# Mini-DSO-WaveGen-in-one.net
KiCad netlist of a schematic drawn in Altium Designer
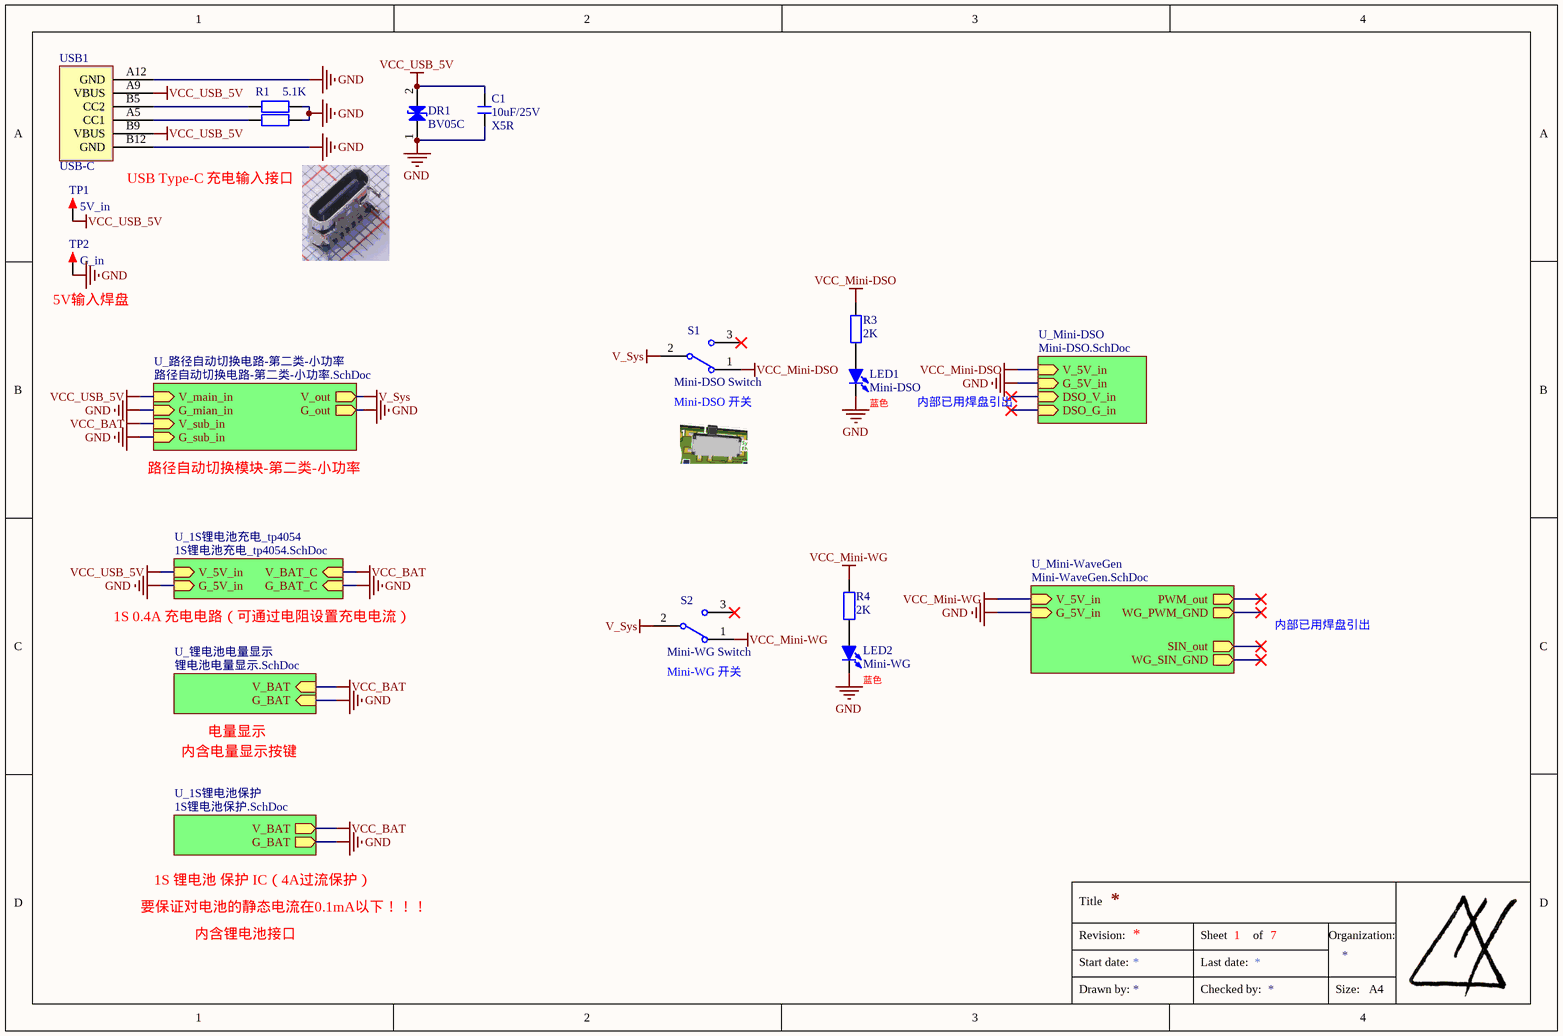
[diagram p0: Mini-DSO-WaveGen-in-one.SchDoc]

(export (version "E")
  (design (tool "Eeschema 10.0.6"))
  (components
    (comp (ref "C1")
      (value "10uF/25V")
      (footprint "C 0603_L")
      (description "无极性贴片电容 X5R")
      (fields (field (name "BOM名称") "X5R"))
      (libsource (lib "Foundation_temp") (part "C X5R"))
    )
    (comp (ref "DR1")
      (value "BV05C")
      (footprint "SOD-323")
      (description "瞬态电压抑制二极管")
      (fields (field (name "版权归属") "源创客"))
      (libsource (lib "8.1   - 二极管-整流桥") (part "DR"))
    )
    (comp (ref "LED1")
      (value "Mini-DSO")
      (footprint "LED 0805R")
      (description "蓝色 贴片LED")
      (fields (field (name "版权归属") "源创客"))
      (libsource (lib "9.1   - LED") (part "LED-SMD"))
    )
    (comp (ref "LED2")
      (value "Mini-WG")
      (footprint "LED 0805R")
      (description "贴片LED 蓝色")
      (fields (field (name "版权归属") "源创客"))
      (libsource (lib "9.1   - LED") (part "LED-SMD"))
    )
    (comp (ref "R1")
      (value "5.1K")
      (footprint "R 0402_L")
      (description "贴片电阻 E-96 1%")
      (libsource (lib "Foundation_temp") (part "R"))
    )
    (comp (ref "R2")
      (value "5.1K")
      (footprint "R 0402_L")
      (description "贴片电阻 E-96 1%")
      (libsource (lib "Foundation_temp") (part "R"))
    )
    (comp (ref "R3")
      (value "2K")
      (footprint "R 0402_L")
      (description "贴片电阻 E-96 1%")
      (libsource (lib "Foundation_temp") (part "R"))
    )
    (comp (ref "R4")
      (value "2K")
      (footprint "R 0402_L")
      (description "贴片电阻 E-96 1%")
      (libsource (lib "Foundation_temp") (part "R"))
    )
    (comp (ref "S1")
      (value "Mini-DSO Switch")
      (footprint "MSK-12C01-07")
      (description "1路拨动开关")
      (fields (field (name "版权归属") "源创客"))
      (libsource (lib "5.1   - 按键-开关") (part "SSW-1P"))
    )
    (comp (ref "S2")
      (value "Mini-WG Switch")
      (footprint "MSK-12C01-07")
      (description "1路拨动开关")
      (fields (field (name "版权归属") "源创客"))
      (libsource (lib "5.1   - 按键-开关") (part "SSW-1P"))
    )
    (comp (ref "TP1")
      (value "5V_in")
      (footprint "TEST 1.6")
      (description "测试点")
      (fields (field (name "版权归属") "源创客"))
      (libsource (lib "15.1 - 未分类器件") (part "TEST"))
    )
    (comp (ref "TP2")
      (value "G_in")
      (footprint "TEST 1.6")
      (description "测试点")
      (fields (field (name "版权归属") "源创客"))
      (libsource (lib "15.1 - 未分类器件") (part "TEST"))
    )
    (comp (ref "USB1")
      (value "USB-C")
      (footprint "USB-C/S_C")
      (description "USB-C_6P型母接口")
      (fields (field (name "版权归属") "源创客"))
      (libsource (lib "4.1   - 接口类") (part "USB-C_6P/S"))
    )
  )
  (nets
    (net (code "7") (name "GND") (class "Default")
      (node (ref "C1") (pin "1") (pinfunction "1_1") (pintype "passive"))
      (node (ref "DR1") (pin "1") (pinfunction "A_1") (pintype "passive"))
      (node (ref "LED1") (pin "2") (pinfunction "K_2") (pintype "passive"))
      (node (ref "LED2") (pin "2") (pinfunction "K_2") (pintype "passive"))
      (node (ref "R1") (pin "1") (pinfunction "1_1") (pintype "passive"))
      (node (ref "R2") (pin "1") (pinfunction "1_1") (pintype "passive"))
      (node (ref "TP2") (pin "1") (pinfunction "1_1") (pintype "passive"))
      (node (ref "USB1") (pin "A12") (pinfunction "GND_A12") (pintype "passive"))
      (node (ref "USB1") (pin "B12") (pinfunction "GND_B12") (pintype "passive"))
    )
    (net (code "8") (name "Net-(LED1-A)") (class "Default")
      (node (ref "LED1") (pin "1") (pinfunction "A_1") (pintype "passive"))
      (node (ref "R3") (pin "2") (pinfunction "2_2") (pintype "passive"))
    )
    (net (code "9") (name "Net-(LED2-A)") (class "Default")
      (node (ref "LED2") (pin "1") (pinfunction "A_1") (pintype "passive"))
      (node (ref "R4") (pin "2") (pinfunction "2_2") (pintype "passive"))
    )
    (net (code "10") (name "Net-(USB1-CC1)") (class "Default")
      (node (ref "R2") (pin "2") (pinfunction "2_2") (pintype "passive"))
      (node (ref "USB1") (pin "A5") (pinfunction "CC1_A5") (pintype "passive"))
    )
    (net (code "11") (name "Net-(USB1-CC2)") (class "Default")
      (node (ref "R1") (pin "2") (pinfunction "2_2") (pintype "passive"))
      (node (ref "USB1") (pin "B5") (pinfunction "CC2_B5") (pintype "passive"))
    )
    (net (code "13") (name "VCC_Mini-DSO") (class "Default")
      (node (ref "R3") (pin "1") (pinfunction "1_1") (pintype "passive"))
      (node (ref "S1") (pin "1") (pinfunction "1_1") (pintype "passive"))
    )
    (net (code "14") (name "VCC_Mini-WG") (class "Default")
      (node (ref "R4") (pin "1") (pinfunction "1_1") (pintype "passive"))
      (node (ref "S2") (pin "1") (pinfunction "1_1") (pintype "passive"))
    )
    (net (code "15") (name "VCC_USB_5V") (class "Default")
      (node (ref "C1") (pin "2") (pinfunction "2_2") (pintype "passive"))
      (node (ref "DR1") (pin "2") (pinfunction "K_2") (pintype "passive"))
      (node (ref "TP1") (pin "1") (pinfunction "1_1") (pintype "passive"))
      (node (ref "USB1") (pin "A9") (pinfunction "VBUS_A9") (pintype "passive"))
      (node (ref "USB1") (pin "B9") (pinfunction "VBUS_B9") (pintype "passive"))
    )
    (net (code "16") (name "V_Sys") (class "Default")
      (node (ref "S1") (pin "2") (pinfunction "2_2") (pintype "passive"))
      (node (ref "S2") (pin "2") (pinfunction "2_2") (pintype "passive"))
    )
    (net (code "17") (name "unconnected-(S1-Pad3)") (class "Default")
      (node (ref "S1") (pin "3") (pinfunction "3_3") (pintype "passive+no_connect"))
    )
    (net (code "18") (name "unconnected-(S2-Pad3)") (class "Default")
      (node (ref "S2") (pin "3") (pinfunction "3_3") (pintype "passive+no_connect"))
    )
  )
)
